# EV_Circuit_Diagram.net
KiCad netlist of a schematic drawn in EAGLE
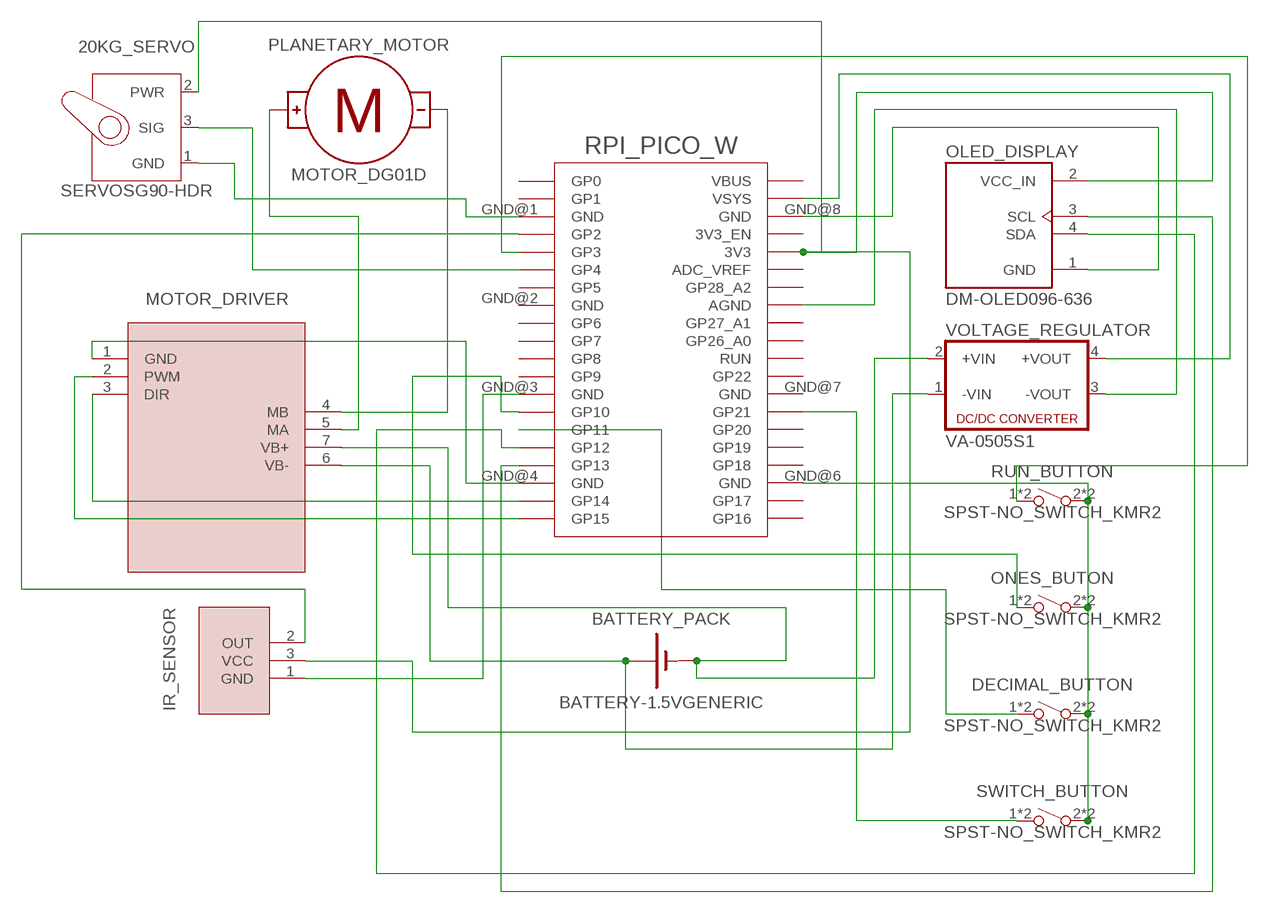
[diagram p0: schematic, sheet 1]

(export (version "E")
  (design (tool "Eeschema 10.0.6"))
  (components
    (comp (ref "20KG_SERVO")
      (value "SERVOSG90-HDR")
      (footprint "eagle-import:1X03")
      (libsource (lib "eagle-import") (part "SERVOSG90-HDR"))
    )
    (comp (ref "BATTERY_PACK")
      (value "BATTERY-1.5VGENERIC")
      (footprint "eagle-import:BATTERY-GENERIC")
      (libsource (lib "eagle-import") (part "BATTERY-1.5VGENERIC"))
    )
    (comp (ref "DECIMAL_BUTTON")
      (value "SPST-NO_SWITCH_KMR2")
      (footprint "eagle-import:KMR2")
      (fields (field (name "MANUFACTURER") "C&K") (field (name "MPN") "KMR211G LFS"))
      (libsource (lib "eagle-import") (part "SPST-NO_SWITCH_KMR2"))
    )
    (comp (ref "IR_SENSOR")
      (value "IR_SENSOR")
      (footprint "eagle-import:IR_SENSOR")
      (libsource (lib "eagle-import") (part "IR_SENSOR"))
    )
    (comp (ref "MD20A_MOTOR_DRIVER")
      (value "CYTRON_MD20A")
      (footprint "eagle-import:MD20A")
      (libsource (lib "eagle-import") (part "CYTRON_MD20A"))
    )
    (comp (ref "OLED_DISPLAY")
      (value "DM-OLED096-636")
      (footprint "eagle-import:MODULE_DM-OLED096-636")
      (fields (field (name "MF") "Display Module"))
      (libsource (lib "eagle-import") (part "DM-OLED096-636"))
    )
    (comp (ref "ONES_BUTON")
      (value "SPST-NO_SWITCH_KMR2")
      (footprint "eagle-import:KMR2")
      (fields (field (name "MANUFACTURER") "C&K") (field (name "MPN") "KMR211G LFS"))
      (libsource (lib "eagle-import") (part "SPST-NO_SWITCH_KMR2"))
    )
    (comp (ref "PLANETARY_MOTOR")
      (value "MOTOR_DG01D")
      (footprint "eagle-import:DG01D")
      (libsource (lib "eagle-import") (part "MOTOR_DG01D"))
    )
    (comp (ref "RPI_PICO_W")
      (value "RPI_PICO_IG-SMD")
      (footprint "eagle-import:RPI_PICO")
      (libsource (lib "eagle-import") (part "RPI_PICO_IG-SMD"))
    )
    (comp (ref "RUN_BUTTON")
      (value "SPST-NO_SWITCH_KMR2")
      (footprint "eagle-import:KMR2")
      (fields (field (name "MANUFACTURER") "C&K") (field (name "MPN") "KMR211G LFS"))
      (libsource (lib "eagle-import") (part "SPST-NO_SWITCH_KMR2"))
    )
    (comp (ref "SWITCH_BUTTON")
      (value "SPST-NO_SWITCH_KMR2")
      (footprint "eagle-import:KMR2")
      (fields (field (name "MANUFACTURER") "C&K") (field (name "MPN") "KMR211G LFS"))
      (libsource (lib "eagle-import") (part "SPST-NO_SWITCH_KMR2"))
    )
    (comp (ref "VOLTAGE_REGULATOR")
      (value "VA-0505S1")
      (footprint "eagle-import:4SIL")
      (libsource (lib "eagle-import") (part "VA-?S10505"))
    )
  )
  (nets
    (net (code "1") (name "Net-(20KG_SERVO-GND)") (class "Default")
      (node (ref "20KG_SERVO") (pin "1") (pinfunction "GND_1") (pintype "bidirectional"))
      (node (ref "RPI_PICO_W") (pin "GND@1") (pinfunction "GND_GND@1") (pintype "bidirectional"))
    )
    (net (code "2") (name "Net-(20KG_SERVO-PWR)") (class "Default")
      (node (ref "20KG_SERVO") (pin "2") (pinfunction "PWR_2") (pintype "bidirectional"))
      (node (ref "IR_SENSOR") (pin "3") (pinfunction "VCC_3") (pintype "input"))
      (node (ref "OLED_DISPLAY") (pin "2") (pinfunction "VCC_IN_2") (pintype "power_in"))
      (node (ref "RPI_PICO_W") (pin "3V3") (pinfunction "3V3_3V3") (pintype "bidirectional"))
    )
    (net (code "3") (name "Net-(20KG_SERVO-SIG)") (class "Default")
      (node (ref "20KG_SERVO") (pin "3") (pinfunction "SIG_3") (pintype "bidirectional"))
      (node (ref "RPI_PICO_W") (pin "GP4") (pinfunction "GP4_GP4") (pintype "bidirectional"))
    )
    (net (code "4") (name "Net-(DECIMAL_BUTTON-1-Pad4)") (class "Default")
      (node (ref "DECIMAL_BUTTON") (pin "1") (pinfunction "1_1") (pintype "passive"))
      (node (ref "DECIMAL_BUTTON") (pin "4") (pinfunction "1_4") (pintype "passive"))
      (node (ref "RPI_PICO_W") (pin "GP11") (pinfunction "GP11_GP11") (pintype "bidirectional"))
    )
    (net (code "5") (name "Net-(DECIMAL_BUTTON-2-Pad3)") (class "Default")
      (node (ref "DECIMAL_BUTTON") (pin "2") (pinfunction "2_2") (pintype "passive"))
      (node (ref "DECIMAL_BUTTON") (pin "3") (pinfunction "2_3") (pintype "passive"))
      (node (ref "ONES_BUTON") (pin "2") (pinfunction "2_2") (pintype "passive"))
      (node (ref "ONES_BUTON") (pin "3") (pinfunction "2_3") (pintype "passive"))
      (node (ref "RPI_PICO_W") (pin "GND@6") (pinfunction "GND_GND@6") (pintype "bidirectional"))
      (node (ref "RUN_BUTTON") (pin "2") (pinfunction "2_2") (pintype "passive"))
      (node (ref "RUN_BUTTON") (pin "3") (pinfunction "2_3") (pintype "passive"))
      (node (ref "SWITCH_BUTTON") (pin "2") (pinfunction "2_2") (pintype "passive"))
      (node (ref "SWITCH_BUTTON") (pin "3") (pinfunction "2_3") (pintype "passive"))
    )
    (net (code "6") (name "Net-(IR_SENSOR-GND)") (class "Default")
      (node (ref "IR_SENSOR") (pin "1") (pinfunction "GND_1") (pintype "input"))
      (node (ref "RPI_PICO_W") (pin "GND@3") (pinfunction "GND_GND@3") (pintype "bidirectional"))
    )
    (net (code "7") (name "Net-(IR_SENSOR-OUT)") (class "Default")
      (node (ref "IR_SENSOR") (pin "2") (pinfunction "OUT_2") (pintype "output"))
      (node (ref "RPI_PICO_W") (pin "GP2") (pinfunction "GP2_GP2") (pintype "bidirectional"))
    )
    (net (code "8") (name "Net-(MD20A_MOTOR_DRIVER-DIR)") (class "Default")
      (node (ref "MD20A_MOTOR_DRIVER") (pin "3") (pinfunction "DIR_3") (pintype "input"))
      (node (ref "RPI_PICO_W") (pin "GP14") (pinfunction "GP14_GP14") (pintype "bidirectional"))
    )
    (net (code "9") (name "Net-(MD20A_MOTOR_DRIVER-GND)") (class "Default")
      (node (ref "MD20A_MOTOR_DRIVER") (pin "1") (pinfunction "GND_1") (pintype "input"))
      (node (ref "RPI_PICO_W") (pin "GND@4") (pinfunction "GND_GND@4") (pintype "bidirectional"))
    )
    (net (code "10") (name "Net-(MD20A_MOTOR_DRIVER-MA)") (class "Default")
      (node (ref "MD20A_MOTOR_DRIVER") (pin "5") (pinfunction "MA_5") (pintype "output"))
      (node (ref "PLANETARY_MOTOR") (pin "+") (pinfunction "+_+") (pintype "passive"))
    )
    (net (code "11") (name "Net-(MD20A_MOTOR_DRIVER-MB)") (class "Default")
      (node (ref "MD20A_MOTOR_DRIVER") (pin "4") (pinfunction "MB_4") (pintype "output"))
      (node (ref "PLANETARY_MOTOR") (pin "-") (pinfunction "-_-") (pintype "passive"))
    )
    (net (code "12") (name "Net-(MD20A_MOTOR_DRIVER-PWM)") (class "Default")
      (node (ref "MD20A_MOTOR_DRIVER") (pin "2") (pinfunction "PWM_2") (pintype "input"))
      (node (ref "RPI_PICO_W") (pin "GP15") (pinfunction "GP15_GP15") (pintype "bidirectional"))
    )
    (net (code "13") (name "Net-(MD20A_MOTOR_DRIVER-VB+)") (class "Default")
      (node (ref "BATTERY_PACK") (pin "-") (pinfunction "-_-") (pintype "passive"))
      (node (ref "MD20A_MOTOR_DRIVER") (pin "7") (pinfunction "VB+_7") (pintype "input"))
      (node (ref "VOLTAGE_REGULATOR") (pin "2") (pinfunction "+VIN_2") (pintype "passive"))
    )
    (net (code "14") (name "Net-(MD20A_MOTOR_DRIVER-VB-)") (class "Default")
      (node (ref "BATTERY_PACK") (pin "+") (pinfunction "+_+") (pintype "passive"))
      (node (ref "MD20A_MOTOR_DRIVER") (pin "6") (pinfunction "VB-_6") (pintype "input"))
      (node (ref "VOLTAGE_REGULATOR") (pin "1") (pinfunction "-VIN_1") (pintype "passive"))
    )
    (net (code "15") (name "Net-(OLED_DISPLAY-GND)") (class "Default")
      (node (ref "OLED_DISPLAY") (pin "1") (pinfunction "GND_1") (pintype "power_in"))
      (node (ref "RPI_PICO_W") (pin "GND@8") (pinfunction "GND_GND@8") (pintype "bidirectional"))
    )
    (net (code "16") (name "Net-(OLED_DISPLAY-SCL)") (class "Default")
      (node (ref "OLED_DISPLAY") (pin "3") (pinfunction "SCL_3") (pintype "input"))
      (node (ref "RPI_PICO_W") (pin "GP13") (pinfunction "GP13_GP13") (pintype "bidirectional"))
    )
    (net (code "17") (name "Net-(OLED_DISPLAY-SDA)") (class "Default")
      (node (ref "OLED_DISPLAY") (pin "4") (pinfunction "SDA_4") (pintype "bidirectional"))
      (node (ref "RPI_PICO_W") (pin "GP12") (pinfunction "GP12_GP12") (pintype "bidirectional"))
    )
    (net (code "18") (name "Net-(ONES_BUTON-1-Pad4)") (class "Default")
      (node (ref "ONES_BUTON") (pin "1") (pinfunction "1_1") (pintype "passive"))
      (node (ref "ONES_BUTON") (pin "4") (pinfunction "1_4") (pintype "passive"))
      (node (ref "RPI_PICO_W") (pin "GP10") (pinfunction "GP10_GP10") (pintype "bidirectional"))
    )
    (net (code "19") (name "Net-(RPI_PICO_W-PadGP3)") (class "Default")
      (node (ref "RPI_PICO_W") (pin "GP3") (pinfunction "GP3_GP3") (pintype "bidirectional"))
      (node (ref "RUN_BUTTON") (pin "1") (pinfunction "1_1") (pintype "passive"))
      (node (ref "RUN_BUTTON") (pin "4") (pinfunction "1_4") (pintype "passive"))
    )
    (net (code "20") (name "Net-(RPI_PICO_W-PadGP21)") (class "Default")
      (node (ref "RPI_PICO_W") (pin "GP21") (pinfunction "GP21_GP21") (pintype "bidirectional"))
      (node (ref "SWITCH_BUTTON") (pin "1") (pinfunction "1_1") (pintype "passive"))
      (node (ref "SWITCH_BUTTON") (pin "4") (pinfunction "1_4") (pintype "passive"))
    )
    (net (code "21") (name "Net-(VOLTAGE_REGULATOR-+VOUT)") (class "Default")
      (node (ref "RPI_PICO_W") (pin "VSYS") (pinfunction "VSYS_VSYS") (pintype "bidirectional"))
      (node (ref "VOLTAGE_REGULATOR") (pin "4") (pinfunction "+VOUT_4") (pintype "passive"))
    )
    (net (code "22") (name "Net-(VOLTAGE_REGULATOR--VOUT)") (class "Default")
      (node (ref "RPI_PICO_W") (pin "AGND") (pinfunction "AGND_AGND") (pintype "bidirectional"))
      (node (ref "VOLTAGE_REGULATOR") (pin "3") (pinfunction "-VOUT_3") (pintype "passive"))
    )
    (net (code "23") (name "unconnected-(RPI_PICO_W-GND-PadGND@2)") (class "Default")
      (node (ref "RPI_PICO_W") (pin "GND@2") (pinfunction "GND_GND@2") (pintype "bidirectional"))
    )
    (net (code "24") (name "unconnected-(RPI_PICO_W-GND-PadGND@7)") (class "Default")
      (node (ref "RPI_PICO_W") (pin "GND@7") (pinfunction "GND_GND@7") (pintype "bidirectional"))
    )
    (net (code "25") (name "unconnected-(RPI_PICO_W-Pad3V3_EN)") (class "Default")
      (node (ref "RPI_PICO_W") (pin "3V3_EN") (pinfunction "3V3_EN_3V3_EN") (pintype "bidirectional"))
    )
    (net (code "26") (name "unconnected-(RPI_PICO_W-PadADC_VREF)") (class "Default")
      (node (ref "RPI_PICO_W") (pin "ADC_VREF") (pinfunction "ADC_VREF_ADC_VREF") (pintype "bidirectional"))
    )
    (net (code "27") (name "unconnected-(RPI_PICO_W-PadGP0)") (class "Default")
      (node (ref "RPI_PICO_W") (pin "GP0") (pinfunction "GP0_GP0") (pintype "bidirectional"))
    )
    (net (code "28") (name "unconnected-(RPI_PICO_W-PadGP1)") (class "Default")
      (node (ref "RPI_PICO_W") (pin "GP1") (pinfunction "GP1_GP1") (pintype "bidirectional"))
    )
    (net (code "29") (name "unconnected-(RPI_PICO_W-PadGP5)") (class "Default")
      (node (ref "RPI_PICO_W") (pin "GP5") (pinfunction "GP5_GP5") (pintype "bidirectional"))
    )
    (net (code "30") (name "unconnected-(RPI_PICO_W-PadGP6)") (class "Default")
      (node (ref "RPI_PICO_W") (pin "GP6") (pinfunction "GP6_GP6") (pintype "bidirectional"))
    )
    (net (code "31") (name "unconnected-(RPI_PICO_W-PadGP7)") (class "Default")
      (node (ref "RPI_PICO_W") (pin "GP7") (pinfunction "GP7_GP7") (pintype "bidirectional"))
    )
    (net (code "32") (name "unconnected-(RPI_PICO_W-PadGP8)") (class "Default")
      (node (ref "RPI_PICO_W") (pin "GP8") (pinfunction "GP8_GP8") (pintype "bidirectional"))
    )
    (net (code "33") (name "unconnected-(RPI_PICO_W-PadGP9)") (class "Default")
      (node (ref "RPI_PICO_W") (pin "GP9") (pinfunction "GP9_GP9") (pintype "bidirectional"))
    )
    (net (code "34") (name "unconnected-(RPI_PICO_W-PadGP16)") (class "Default")
      (node (ref "RPI_PICO_W") (pin "GP16") (pinfunction "GP16_GP16") (pintype "bidirectional"))
    )
    (net (code "35") (name "unconnected-(RPI_PICO_W-PadGP17)") (class "Default")
      (node (ref "RPI_PICO_W") (pin "GP17") (pinfunction "GP17_GP17") (pintype "bidirectional"))
    )
    (net (code "36") (name "unconnected-(RPI_PICO_W-PadGP18)") (class "Default")
      (node (ref "RPI_PICO_W") (pin "GP18") (pinfunction "GP18_GP18") (pintype "bidirectional"))
    )
    (net (code "37") (name "unconnected-(RPI_PICO_W-PadGP19)") (class "Default")
      (node (ref "RPI_PICO_W") (pin "GP19") (pinfunction "GP19_GP19") (pintype "bidirectional"))
    )
    (net (code "38") (name "unconnected-(RPI_PICO_W-PadGP20)") (class "Default")
      (node (ref "RPI_PICO_W") (pin "GP20") (pinfunction "GP20_GP20") (pintype "bidirectional"))
    )
    (net (code "39") (name "unconnected-(RPI_PICO_W-PadGP22)") (class "Default")
      (node (ref "RPI_PICO_W") (pin "GP22") (pinfunction "GP22_GP22") (pintype "bidirectional"))
    )
    (net (code "40") (name "unconnected-(RPI_PICO_W-PadGP26_A0)") (class "Default")
      (node (ref "RPI_PICO_W") (pin "GP26_A0") (pinfunction "GP26_A0_GP26_A0") (pintype "bidirectional"))
    )
    (net (code "41") (name "unconnected-(RPI_PICO_W-PadGP27_A1)") (class "Default")
      (node (ref "RPI_PICO_W") (pin "GP27_A1") (pinfunction "GP27_A1_GP27_A1") (pintype "bidirectional"))
    )
    (net (code "42") (name "unconnected-(RPI_PICO_W-PadGP28_A2)") (class "Default")
      (node (ref "RPI_PICO_W") (pin "GP28_A2") (pinfunction "GP28_A2_GP28_A2") (pintype "bidirectional"))
    )
    (net (code "43") (name "unconnected-(RPI_PICO_W-PadRUN)") (class "Default")
      (node (ref "RPI_PICO_W") (pin "RUN") (pinfunction "RUN_RUN") (pintype "bidirectional"))
    )
    (net (code "44") (name "unconnected-(RPI_PICO_W-PadVBUS)") (class "Default")
      (node (ref "RPI_PICO_W") (pin "VBUS") (pinfunction "VBUS_VBUS") (pintype "bidirectional"))
    )
  )
)
